# SymphonyLights_MCU_v1_0.net
KiCad netlist of a schematic drawn in Altium Designer
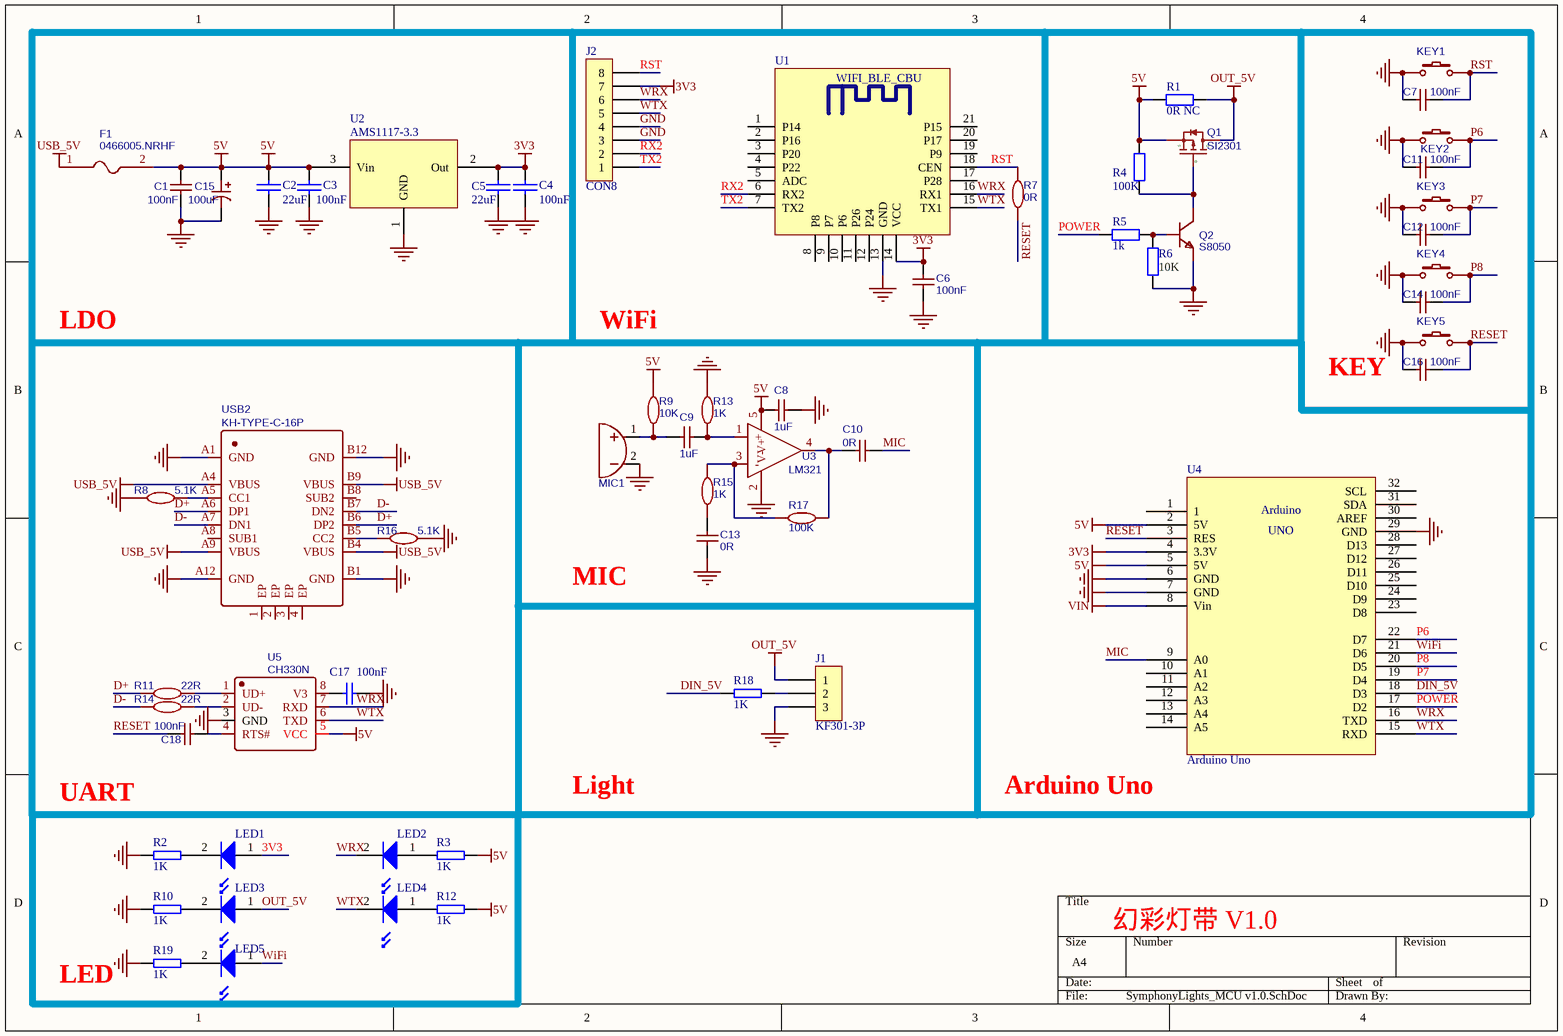
[diagram p0: SymphonyLights_MCU v1.0.SchDoc]

(export (version "E")
  (design (tool "Eeschema 10.0.6"))
  (components
    (comp (ref "C1")
      (value "100nF")
      (footprint "0805C")
      (fields
        (field (name "BOM_MANUFACTURER PART") "0805B104K500NT")
        (field (name "BOM_SUPPLIER PART") "C38141")
      )
      (libsource (lib "altium-import") (part "root_1_100nF_"))
    )
    (comp (ref "C2")
      (value "22uF")
      (footprint "0805C")
      (description "Capacitor")
      (libsource (lib "昊华元件库sch") (part "CAP"))
    )
    (comp (ref "C3")
      (value "100nF")
      (footprint "0805C")
      (description "Capacitor")
      (libsource (lib "昊华元件库sch") (part "CAP"))
    )
    (comp (ref "C4")
      (value "100nF")
      (footprint "0805C")
      (description "Capacitor")
      (libsource (lib "昊华元件库sch") (part "CAP"))
    )
    (comp (ref "C5")
      (value "22uF")
      (footprint "0805C")
      (description "Capacitor")
      (libsource (lib "昊华元件库sch") (part "CAP"))
    )
    (comp (ref "C6")
      (value "100nF")
      (footprint "0805C")
      (fields
        (field (name "BOM_MANUFACTURER PART") "0805B104K500NT")
        (field (name "BOM_SUPPLIER PART") "C38141")
      )
      (libsource (lib "altium-import") (part "root_1_100nF_"))
    )
    (comp (ref "C7")
      (value "100nF")
      (footprint "0805C")
      (fields
        (field (name "BOM_MANUFACTURER PART") "0805B104K500NT")
        (field (name "BOM_SUPPLIER PART") "C38141")
      )
      (libsource (lib "altium-import") (part "root_0_100nF_"))
    )
    (comp (ref "C8")
      (value "1uF")
      (footprint "0805C")
      (fields
        (field (name "BOM_MANUFACTURER PART") "0805B104K500NT")
        (field (name "BOM_SUPPLIER PART") "C38141")
      )
      (libsource (lib "altium-import") (part "root_0_100nF_"))
    )
    (comp (ref "C9")
      (value "1uF")
      (footprint "0805C")
      (fields
        (field (name "BOM_MANUFACTURER PART") "0805B104K500NT")
        (field (name "BOM_SUPPLIER PART") "C38141")
      )
      (libsource (lib "altium-import") (part "root_2_100nF_"))
    )
    (comp (ref "C10")
      (value "0R")
      (footprint "0805C")
      (fields
        (field (name "BOM_MANUFACTURER PART") "0805B104K500NT")
        (field (name "BOM_SUPPLIER PART") "C38141")
      )
      (libsource (lib "altium-import") (part "root_2_100nF_"))
    )
    (comp (ref "C11")
      (value "100nF")
      (footprint "0805C")
      (fields
        (field (name "BOM_MANUFACTURER PART") "0805B104K500NT")
        (field (name "BOM_SUPPLIER PART") "C38141")
      )
      (libsource (lib "altium-import") (part "root_0_100nF_"))
    )
    (comp (ref "C12")
      (value "100nF")
      (footprint "0805C")
      (fields
        (field (name "BOM_MANUFACTURER PART") "0805B104K500NT")
        (field (name "BOM_SUPPLIER PART") "C38141")
      )
      (libsource (lib "altium-import") (part "root_0_100nF_"))
    )
    (comp (ref "C13")
      (value "0R")
      (footprint "0805C")
      (fields
        (field (name "BOM_MANUFACTURER PART") "0805B104K500NT")
        (field (name "BOM_SUPPLIER PART") "C38141")
      )
      (libsource (lib "altium-import") (part "root_3_100nF_"))
    )
    (comp (ref "C14")
      (value "100nF")
      (footprint "0805C")
      (fields
        (field (name "BOM_MANUFACTURER PART") "0805B104K500NT")
        (field (name "BOM_SUPPLIER PART") "C38141")
      )
      (libsource (lib "altium-import") (part "root_0_100nF_"))
    )
    (comp (ref "C15")
      (value "100uF")
      (footprint "CAP-TH_BD6.3-P2.50-D1.0-FD")
      (fields
        (field (name "BOM_SUPPLIER PART") "C723077")
        (field (name "BOM_MANUFACTURER PART") "8101LCMAA08E2RR00O")
        (field (name "CONTRIBUTOR") "LCSC")
      )
      (libsource (lib "altium-import") (part "root_3_8101LCMAA08E2RR00O_"))
    )
    (comp (ref "C16")
      (value "100nF")
      (footprint "0805C")
      (fields
        (field (name "BOM_MANUFACTURER PART") "0805B104K500NT")
        (field (name "BOM_SUPPLIER PART") "C38141")
      )
      (libsource (lib "altium-import") (part "root_0_100nF_"))
    )
    (comp (ref "C17")
      (value "100nF")
      (footprint "0805C")
      (description "普通电容")
      (libsource (lib "RFID_RC632") (part "Cap"))
    )
    (comp (ref "C18")
      (value "100nF")
      (footprint "0805C")
      (fields
        (field (name "BOM_MANUFACTURER PART") "0805B104K500NT")
        (field (name "BOM_SUPPLIER PART") "C38141")
      )
      (libsource (lib "altium-import") (part "root_0_100nF_"))
    )
    (comp (ref "F1")
      (value "0466005.NRHF")
      (footprint "1206F")
      (fields (field (name "BOM_SUPPLIER PART") "C57525"))
      (libsource (lib "altium-import") (part "root_0_0466005.NRHF_"))
    )
    (comp (ref "J1")
      (value "KF301-3P")
      (footprint "SIP3 - 2.54")
      (description "Connector")
      (libsource (lib "小马元件库sch") (part "CON3"))
    )
    (comp (ref "J2")
      (value "CON8")
      (footprint "HDR1X8Z")
      (description "Connector")
      (libsource (lib "小马元件库sch") (part "CON8"))
    )
    (comp (ref "KEY1")
      (value "RESET")
      (footprint "按键")
      (fields
        (field (name "BOM_SUPPLIER PART") "C118141")
        (field (name "BOM_MANUFACTURER PART") "K2-1107ST-A4SW-06")
        (field (name "CONTRIBUTOR") "LCEDA_Lib")
      )
      (libsource (lib "altium-import") (part "root_2_mirrored__"))
    )
    (comp (ref "KEY2")
      (value "场景")
      (footprint "按键")
      (fields
        (field (name "BOM_SUPPLIER PART") "C118141")
        (field (name "BOM_MANUFACTURER PART") "K2-1107ST-A4SW-06")
        (field (name "CONTRIBUTOR") "LCEDA_Lib")
      )
      (libsource (lib "altium-import") (part "root_2__"))
    )
    (comp (ref "KEY3")
      (value "音乐")
      (footprint "按键")
      (fields
        (field (name "BOM_SUPPLIER PART") "C118141")
        (field (name "BOM_MANUFACTURER PART") "K2-1107ST-A4SW-06")
        (field (name "CONTRIBUTOR") "LCEDA_Lib")
      )
      (libsource (lib "altium-import") (part "root_2_mirrored__"))
    )
    (comp (ref "KEY4")
      (value "开关")
      (footprint "按键")
      (fields
        (field (name "BOM_SUPPLIER PART") "C118141")
        (field (name "BOM_MANUFACTURER PART") "K2-1107ST-A4SW-06")
        (field (name "CONTRIBUTOR") "LCEDA_Lib")
      )
      (libsource (lib "altium-import") (part "root_2_mirrored__"))
    )
    (comp (ref "KEY5")
      (value "开关")
      (footprint "按键")
      (fields
        (field (name "BOM_SUPPLIER PART") "C118141")
        (field (name "BOM_MANUFACTURER PART") "K2-1107ST-A4SW-06")
        (field (name "CONTRIBUTOR") "LCEDA_Lib")
      )
      (libsource (lib "altium-import") (part "root_2_mirrored__"))
    )
    (comp (ref "LED1")
      (value "LED")
      (footprint "0805LED")
      (fields (field (name "PUBLISHER") "*"))
      (libsource (lib "小马元件库sch") (part "LED"))
    )
    (comp (ref "LED2")
      (value "LED")
      (footprint "0805LED")
      (fields (field (name "PUBLISHER") "*"))
      (libsource (lib "小马元件库sch") (part "LED"))
    )
    (comp (ref "LED3")
      (value "LED")
      (footprint "0805LED")
      (fields (field (name "PUBLISHER") "*"))
      (libsource (lib "小马元件库sch") (part "LED"))
    )
    (comp (ref "LED4")
      (value "LED")
      (footprint "0805LED")
      (fields (field (name "PUBLISHER") "*"))
      (libsource (lib "小马元件库sch") (part "LED"))
    )
    (comp (ref "LED5")
      (value "LED")
      (footprint "0805LED")
      (fields (field (name "PUBLISHER") "*"))
      (libsource (lib "小马元件库sch") (part "LED"))
    )
    (comp (ref "MIC1")
      (value "GMI6050P-66DB")
      (footprint "MIC-TH_BD6.0-P1.90-D0.4-L-RD")
      (fields (field (name "BOM_SUPPLIER PART") "C233954") (field (name "CONTRIBUTOR") "LCSC"))
      (libsource (lib "altium-import") (part "root_3_mirrored_GMI6050P-66DB_"))
    )
    (comp (ref "Q1")
      (value "SI2301")
      (footprint "SOT-23(SOT-23-3)")
      (fields (field (name "BOM_SUPPLIER PART") "C181086") (field (name "CONTRIBUTOR") "lengyuefeng"))
      (libsource (lib "altium-import") (part "root_1_mirrored_SI2301_"))
    )
    (comp (ref "Q2")
      (value "S8050")
      (footprint "SOT-23(SOT-23-3)")
      (fields (field (name "BOM_SUPPLIER PART") "C2146"))
      (libsource (lib "altium-import") (part "root_0_S8050_"))
    )
    (comp (ref "R1")
      (value "0R NC")
      (footprint "0805R")
      (description "Resistor")
      (fields (field (name "PUBLISHER") "Altium Limited"))
      (libsource (lib "*") (part "Res2"))
    )
    (comp (ref "R2") (value "1K") (footprint "0805R") (libsource (lib "昊华元件库sch") (part "RES5")))
    (comp (ref "R3") (value "1K") (footprint "0805R") (libsource (lib "昊华元件库sch") (part "RES5")))
    (comp (ref "R4")
      (value "100K")
      (footprint "0805R")
      (description "Resistor")
      (fields (field (name "PUBLISHER") "Altium Limited"))
      (libsource (lib "") (part "Res2_2"))
    )
    (comp (ref "R5")
      (value "1k")
      (footprint "0805R")
      (description "Resistor")
      (fields (field (name "PUBLISHER") "Altium Limited"))
      (libsource (lib "*") (part "Res2"))
    )
    (comp (ref "R6")
      (value "10K")
      (footprint "0805R")
      (description "Resistor")
      (fields (field (name "PUBLISHER") "Altium Limited"))
      (libsource (lib "") (part "Res2_1"))
    )
    (comp (ref "R7")
      (value "0R")
      (footprint "0805R")
      (fields
        (field (name "BOM_SUPPLIER PART") "C328298")
        (field (name "BOM_MANUFACTURER PART") "AECR0402F10K0K9")
        (field (name "CONTRIBUTOR") "LCSC")
      )
      (libsource (lib "altium-import") (part "root_3_10K_"))
    )
    (comp (ref "R8")
      (value "5.1K")
      (footprint "0805R")
      (fields
        (field (name "BOM_SUPPLIER PART") "C328298")
        (field (name "BOM_MANUFACTURER PART") "AECR0402F10K0K9")
        (field (name "CONTRIBUTOR") "LCSC")
      )
      (libsource (lib "altium-import") (part "root_0_10K_"))
    )
    (comp (ref "R9")
      (value "10K")
      (footprint "0805R")
      (fields
        (field (name "BOM_SUPPLIER PART") "C328298")
        (field (name "BOM_MANUFACTURER PART") "AECR0402F10K0K9")
        (field (name "CONTRIBUTOR") "LCSC")
      )
      (libsource (lib "altium-import") (part "root_3_10K_"))
    )
    (comp (ref "R10") (value "1K") (footprint "0805R") (libsource (lib "昊华元件库sch") (part "RES5")))
    (comp (ref "R11")
      (value "22R")
      (footprint "0805R")
      (fields
        (field (name "BOM_SUPPLIER PART") "C328298")
        (field (name "BOM_MANUFACTURER PART") "AECR0402F10K0K9")
        (field (name "CONTRIBUTOR") "LCSC")
      )
      (libsource (lib "altium-import") (part "root_2_10K_"))
    )
    (comp (ref "R12") (value "1K") (footprint "0805R") (libsource (lib "昊华元件库sch") (part "RES5")))
    (comp (ref "R13")
      (value "1K")
      (footprint "0805R")
      (fields
        (field (name "BOM_SUPPLIER PART") "C328298")
        (field (name "BOM_MANUFACTURER PART") "AECR0402F10K0K9")
        (field (name "CONTRIBUTOR") "LCSC")
      )
      (libsource (lib "altium-import") (part "root_3_10K_"))
    )
    (comp (ref "R14")
      (value "22R")
      (footprint "0805R")
      (fields
        (field (name "BOM_SUPPLIER PART") "C328298")
        (field (name "BOM_MANUFACTURER PART") "AECR0402F10K0K9")
        (field (name "CONTRIBUTOR") "LCSC")
      )
      (libsource (lib "altium-import") (part "root_2_10K_"))
    )
    (comp (ref "R15")
      (value "1K")
      (footprint "0805R")
      (fields
        (field (name "BOM_SUPPLIER PART") "C328298")
        (field (name "BOM_MANUFACTURER PART") "AECR0402F10K0K9")
        (field (name "CONTRIBUTOR") "LCSC")
      )
      (libsource (lib "altium-import") (part "root_1_10K_"))
    )
    (comp (ref "R16")
      (value "5.1K")
      (footprint "0805R")
      (fields
        (field (name "BOM_SUPPLIER PART") "C328298")
        (field (name "BOM_MANUFACTURER PART") "AECR0402F10K0K9")
        (field (name "CONTRIBUTOR") "LCSC")
      )
      (libsource (lib "altium-import") (part "root_2_10K_"))
    )
    (comp (ref "R17")
      (value "100K")
      (footprint "0805R")
      (fields
        (field (name "BOM_SUPPLIER PART") "C328298")
        (field (name "BOM_MANUFACTURER PART") "AECR0402F10K0K9")
        (field (name "CONTRIBUTOR") "LCSC")
      )
      (libsource (lib "altium-import") (part "root_0_10K_"))
    )
    (comp (ref "R18") (value "1K") (footprint "0805R") (libsource (lib "昊华元件库sch") (part "RES5")))
    (comp (ref "R19") (value "1K") (footprint "0805R") (libsource (lib "昊华元件库sch") (part "RES5")))
    (comp (ref "U1")
      (value "WIFI_BLE_CBU")
      (footprint "WIFI_BLE_CBU")
      (description "Module")
      (libsource (lib "TYModeSchlib V03") (part "WIFI_BLE_CBU"))
    )
    (comp (ref "U2") (value "AMS1117-3.3") (footprint "SOT-223") (libsource (lib "mylib") (part "GM1117")))
    (comp (ref "U3")
      (value "LM321")
      (footprint "SOT-23-5")
      (fields (field (name "CONTRIBUTOR") "KiCAD"))
      (libsource (lib "altium-import") (part "root_0_LM321_"))
    )
    (comp (ref "U4")
      (value "Arduino Uno")
      (footprint "Arduino UNO-2")
      (libsource (lib "Arduino") (part "Arduino Uno"))
    )
    (comp (ref "U5")
      (value "CH330N")
      (footprint "SOP-8_L4.9-W3.9-P1.27-LS6.0-BL")
      (fields (field (name "BOM_SUPPLIER PART") "C108996"))
      (libsource (lib "altium-import") (part "root_0_CH330N_"))
    )
    (comp (ref "USB2")
      (value "KH-TYPE-C-16P")
      (footprint "USB-C-SMD_KH-TYPE-C-16P")
      (fields (field (name "BOM_SUPPLIER PART") "C709357") (field (name "CONTRIBUTOR") "LCSC"))
      (libsource (lib "altium-import") (part "root_0_KH-TYPE-C-16P_"))
    )
  )
  (nets
    (net (code "1") (name "/D+") (class "Default")
      (node (ref "R11") (pin "2") (pinfunction "2_2") (pintype "passive"))
      (node (ref "USB2") (pin "A6") (pinfunction "DP1_A6") (pintype "passive"))
      (node (ref "USB2") (pin "B6") (pinfunction "DP2_B6") (pintype "passive"))
    )
    (net (code "2") (name "/D-") (class "Default")
      (node (ref "R14") (pin "2") (pinfunction "2_2") (pintype "passive"))
      (node (ref "USB2") (pin "A7") (pinfunction "DN1_A7") (pintype "passive"))
      (node (ref "USB2") (pin "B7") (pinfunction "DN2_B7") (pintype "passive"))
    )
    (net (code "3") (name "/DIN_5V") (class "Default")
      (node (ref "R18") (pin "1") (pinfunction "1_1") (pintype "passive"))
      (node (ref "U4") (pin "18") (pinfunction "D3_18") (pintype "passive"))
    )
    (net (code "4") (name "/MIC") (class "Default")
      (node (ref "C10") (pin "1") (pinfunction "1_1") (pintype "passive"))
      (node (ref "U4") (pin "9") (pinfunction "A0_9") (pintype "passive"))
    )
    (net (code "5") (name "/P6") (class "Default")
      (node (ref "C11") (pin "2") (pinfunction "2_2") (pintype "passive"))
      (node (ref "KEY2") (pin "2") (pinfunction "2_2") (pintype "passive"))
      (node (ref "U4") (pin "22") (pinfunction "D7_22") (pintype "passive"))
    )
    (net (code "6") (name "/P7") (class "Default")
      (node (ref "C12") (pin "2") (pinfunction "2_2") (pintype "passive"))
      (node (ref "KEY3") (pin "1") (pinfunction "1_1") (pintype "passive"))
      (node (ref "U4") (pin "19") (pinfunction "D4_19") (pintype "passive"))
    )
    (net (code "7") (name "/P8") (class "Default")
      (node (ref "C14") (pin "2") (pinfunction "2_2") (pintype "passive"))
      (node (ref "KEY4") (pin "1") (pinfunction "1_1") (pintype "passive"))
      (node (ref "U4") (pin "20") (pinfunction "D5_20") (pintype "passive"))
    )
    (net (code "8") (name "/POWER") (class "Default")
      (node (ref "R5") (pin "1") (pinfunction "1_1") (pintype "passive"))
      (node (ref "U4") (pin "17") (pinfunction "D2_17") (pintype "passive"))
    )
    (net (code "9") (name "/RESET") (class "Default")
      (node (ref "C16") (pin "2") (pinfunction "2_2") (pintype "passive"))
      (node (ref "C18") (pin "1") (pinfunction "1_1") (pintype "passive"))
      (node (ref "KEY5") (pin "1") (pinfunction "1_1") (pintype "passive"))
      (node (ref "R7") (pin "2") (pinfunction "2_2") (pintype "passive"))
      (node (ref "U4") (pin "3") (pinfunction "RES_3") (pintype "passive"))
    )
    (net (code "10") (name "/RST") (class "Default")
      (node (ref "C7") (pin "2") (pinfunction "2_2") (pintype "passive"))
      (node (ref "J2") (pin "8") (pinfunction "8_8") (pintype "passive"))
      (node (ref "KEY1") (pin "1") (pinfunction "1_1") (pintype "passive"))
      (node (ref "R7") (pin "1") (pinfunction "1_1") (pintype "passive"))
      (node (ref "U1") (pin "18") (pinfunction "CEN_18") (pintype "passive"))
    )
    (net (code "11") (name "/RX2") (class "Default")
      (node (ref "J2") (pin "2") (pinfunction "2_2") (pintype "passive"))
      (node (ref "U1") (pin "6") (pinfunction "RX2_6") (pintype "passive"))
    )
    (net (code "12") (name "/TX2") (class "Default")
      (node (ref "J2") (pin "1") (pinfunction "1_1") (pintype "passive"))
      (node (ref "U1") (pin "7") (pinfunction "TX2_7") (pintype "passive"))
    )
    (net (code "13") (name "/WRX") (class "Default")
      (node (ref "J2") (pin "6") (pinfunction "6_6") (pintype "passive"))
      (node (ref "LED2") (pin "2") (pinfunction "2_2") (pintype "passive"))
      (node (ref "U1") (pin "16") (pinfunction "RX1_16") (pintype "passive"))
      (node (ref "U4") (pin "16") (pinfunction "TXD_16") (pintype "passive"))
      (node (ref "U5") (pin "7") (pinfunction "RXD_7") (pintype "passive"))
    )
    (net (code "14") (name "/WTX") (class "Default")
      (node (ref "J2") (pin "5") (pinfunction "5_5") (pintype "passive"))
      (node (ref "LED4") (pin "2") (pinfunction "2_2") (pintype "passive"))
      (node (ref "U1") (pin "15") (pinfunction "TX1_15") (pintype "passive"))
      (node (ref "U4") (pin "15") (pinfunction "RXD_15") (pintype "passive"))
      (node (ref "U5") (pin "6") (pinfunction "TXD_6") (pintype "passive"))
    )
    (net (code "15") (name "/WiFi") (class "Default")
      (node (ref "LED5") (pin "1") (pinfunction "1_1") (pintype "passive"))
      (node (ref "U4") (pin "21") (pinfunction "D6_21") (pintype "passive"))
    )
    (net (code "16") (name "3V3") (class "Default")
      (node (ref "C4") (pin "1") (pinfunction "1_1") (pintype "passive"))
      (node (ref "C5") (pin "1") (pinfunction "1_1") (pintype "passive"))
      (node (ref "C6") (pin "2") (pinfunction "2_2") (pintype "passive"))
      (node (ref "J2") (pin "7") (pinfunction "7_7") (pintype "passive"))
      (node (ref "LED1") (pin "1") (pinfunction "1_1") (pintype "passive"))
      (node (ref "U1") (pin "14") (pinfunction "VCC_14") (pintype "passive"))
      (node (ref "U2") (pin "2") (pinfunction "Out_2") (pintype "passive"))
      (node (ref "U4") (pin "4") (pinfunction "3.3V_4") (pintype "passive"))
    )
    (net (code "17") (name "5V") (class "Default")
      (node (ref "C1") (pin "2") (pinfunction "2_2") (pintype "passive"))
      (node (ref "C15") (pin "1") (pinfunction "1_1") (pintype "passive"))
      (node (ref "C2") (pin "1") (pinfunction "1_1") (pintype "passive"))
      (node (ref "C3") (pin "1") (pinfunction "1_1") (pintype "passive"))
      (node (ref "C8") (pin "1") (pinfunction "1_1") (pintype "passive"))
      (node (ref "F1") (pin "2") (pinfunction "2_2") (pintype "passive"))
      (node (ref "Q1") (pin "2") (pinfunction "S_2") (pintype "passive"))
      (node (ref "R1") (pin "1") (pinfunction "1_1") (pintype "passive"))
      (node (ref "R12") (pin "1") (pinfunction "1_1") (pintype "passive"))
      (node (ref "R3") (pin "1") (pinfunction "1_1") (pintype "passive"))
      (node (ref "R4") (pin "2") (pinfunction "2_2") (pintype "passive"))
      (node (ref "R9") (pin "1") (pinfunction "1_1") (pintype "passive"))
      (node (ref "U2") (pin "3") (pinfunction "Vin_3") (pintype "passive"))
      (node (ref "U3") (pin "5") (pinfunction "V+_5") (pintype "passive"))
      (node (ref "U4") (pin "2") (pinfunction "5V_2") (pintype "passive"))
      (node (ref "U4") (pin "5") (pinfunction "5V_5") (pintype "passive"))
      (node (ref "U5") (pin "5") (pinfunction "VCC_5") (pintype "passive"))
    )
    (net (code "18") (name "GND") (class "Default")
      (node (ref "C1") (pin "1") (pinfunction "1_1") (pintype "passive"))
      (node (ref "C11") (pin "1") (pinfunction "1_1") (pintype "passive"))
      (node (ref "C12") (pin "1") (pinfunction "1_1") (pintype "passive"))
      (node (ref "C13") (pin "2") (pinfunction "2_2") (pintype "passive"))
      (node (ref "C14") (pin "1") (pinfunction "1_1") (pintype "passive"))
      (node (ref "C15") (pin "2") (pinfunction "2_2") (pintype "passive"))
      (node (ref "C16") (pin "1") (pinfunction "1_1") (pintype "passive"))
      (node (ref "C17") (pin "1") (pinfunction "1_1") (pintype "passive"))
      (node (ref "C2") (pin "2") (pinfunction "2_2") (pintype "passive"))
      (node (ref "C3") (pin "2") (pinfunction "2_2") (pintype "passive"))
      (node (ref "C4") (pin "2") (pinfunction "2_2") (pintype "passive"))
      (node (ref "C5") (pin "2") (pinfunction "2_2") (pintype "passive"))
      (node (ref "C6") (pin "1") (pinfunction "1_1") (pintype "passive"))
      (node (ref "C7") (pin "1") (pinfunction "1_1") (pintype "passive"))
      (node (ref "C8") (pin "2") (pinfunction "2_2") (pintype "passive"))
      (node (ref "J1") (pin "3") (pinfunction "3_3") (pintype "passive"))
      (node (ref "J2") (pin "3") (pinfunction "3_3") (pintype "passive"))
      (node (ref "J2") (pin "4") (pinfunction "4_4") (pintype "passive"))
      (node (ref "KEY1") (pin "2") (pinfunction "2_2") (pintype "passive"))
      (node (ref "KEY2") (pin "1") (pinfunction "1_1") (pintype "passive"))
      (node (ref "KEY3") (pin "2") (pinfunction "2_2") (pintype "passive"))
      (node (ref "KEY4") (pin "2") (pinfunction "2_2") (pintype "passive"))
      (node (ref "KEY5") (pin "2") (pinfunction "2_2") (pintype "passive"))
      (node (ref "MIC1") (pin "2") (pinfunction "2_2") (pintype "passive"))
      (node (ref "Q2") (pin "2") (pinfunction "E_2") (pintype "passive"))
      (node (ref "R10") (pin "2") (pinfunction "2_2") (pintype "passive"))
      (node (ref "R13") (pin "1") (pinfunction "1_1") (pintype "passive"))
      (node (ref "R16") (pin "1") (pinfunction "1_1") (pintype "passive"))
      (node (ref "R19") (pin "2") (pinfunction "2_2") (pintype "passive"))
      (node (ref "R2") (pin "2") (pinfunction "2_2") (pintype "passive"))
      (node (ref "R6") (pin "2") (pinfunction "2_2") (pintype "passive"))
      (node (ref "R8") (pin "1") (pinfunction "1_1") (pintype "passive"))
      (node (ref "U1") (pin "13") (pinfunction "GND_13") (pintype "passive"))
      (node (ref "U2") (pin "1") (pinfunction "GND_1") (pintype "passive"))
      (node (ref "U3") (pin "2") (pinfunction "V-_2") (pintype "passive"))
      (node (ref "U4") (pin "29") (pinfunction "GND_29") (pintype "passive"))
      (node (ref "U4") (pin "6") (pinfunction "GND_6") (pintype "passive"))
      (node (ref "U4") (pin "7") (pinfunction "GND_7") (pintype "passive"))
      (node (ref "U5") (pin "3") (pinfunction "GND_3") (pintype "passive"))
      (node (ref "USB2") (pin "A1") (pinfunction "GND_A1") (pintype "passive"))
      (node (ref "USB2") (pin "A12") (pinfunction "GND_A12") (pintype "passive"))
      (node (ref "USB2") (pin "B1") (pinfunction "GND_B1") (pintype "passive"))
      (node (ref "USB2") (pin "B12") (pinfunction "GND_B12") (pintype "passive"))
    )
    (net (code "19") (name "Net-(C9-Pad2)") (class "Default")
      (node (ref "C9") (pin "2") (pinfunction "2_2") (pintype "passive"))
      (node (ref "MIC1") (pin "1") (pinfunction "1_1") (pintype "passive"))
      (node (ref "R9") (pin "2") (pinfunction "2_2") (pintype "passive"))
    )
    (net (code "20") (name "Net-(C10-Pad2)") (class "Default")
      (node (ref "C10") (pin "2") (pinfunction "2_2") (pintype "passive"))
      (node (ref "R17") (pin "2") (pinfunction "2_2") (pintype "passive"))
      (node (ref "U3") (pin "4") (pintype "passive"))
    )
    (net (code "21") (name "Net-(C13-Pad1)") (class "Default")
      (node (ref "C13") (pin "1") (pinfunction "1_1") (pintype "passive"))
      (node (ref "R15") (pin "1") (pinfunction "1_1") (pintype "passive"))
    )
    (net (code "22") (name "Net-(J1-Pad2)") (class "Default")
      (node (ref "J1") (pin "2") (pinfunction "2_2") (pintype "passive"))
      (node (ref "R18") (pin "2") (pinfunction "2_2") (pintype "passive"))
    )
    (net (code "23") (name "Net-(LED1-Pad2)") (class "Default")
      (node (ref "LED1") (pin "2") (pinfunction "2_2") (pintype "passive"))
      (node (ref "R2") (pin "1") (pinfunction "1_1") (pintype "passive"))
    )
    (net (code "24") (name "Net-(LED2-Pad1)") (class "Default")
      (node (ref "LED2") (pin "1") (pinfunction "1_1") (pintype "passive"))
      (node (ref "R3") (pin "2") (pinfunction "2_2") (pintype "passive"))
    )
    (net (code "25") (name "Net-(LED3-Pad2)") (class "Default")
      (node (ref "LED3") (pin "2") (pinfunction "2_2") (pintype "passive"))
      (node (ref "R10") (pin "1") (pinfunction "1_1") (pintype "passive"))
    )
    (net (code "26") (name "Net-(LED4-Pad1)") (class "Default")
      (node (ref "LED4") (pin "1") (pinfunction "1_1") (pintype "passive"))
      (node (ref "R12") (pin "2") (pinfunction "2_2") (pintype "passive"))
    )
    (net (code "27") (name "Net-(LED5-Pad2)") (class "Default")
      (node (ref "LED5") (pin "2") (pinfunction "2_2") (pintype "passive"))
      (node (ref "R19") (pin "1") (pinfunction "1_1") (pintype "passive"))
    )
    (net (code "28") (name "Net-(Q1-G)") (class "Default")
      (node (ref "Q1") (pin "1") (pinfunction "G_1") (pintype "passive"))
      (node (ref "Q2") (pin "3") (pinfunction "C_3") (pintype "passive"))
      (node (ref "R4") (pin "1") (pinfunction "1_1") (pintype "passive"))
    )
    (net (code "29") (name "Net-(Q2-B)") (class "Default")
      (node (ref "Q2") (pin "1") (pinfunction "B_1") (pintype "passive"))
      (node (ref "R5") (pin "2") (pinfunction "2_2") (pintype "passive"))
      (node (ref "R6") (pin "1") (pinfunction "1_1") (pintype "passive"))
    )
    (net (code "30") (name "Net-(U3-+)") (class "Default")
      (node (ref "C9") (pin "1") (pinfunction "1_1") (pintype "passive"))
      (node (ref "R13") (pin "2") (pinfunction "2_2") (pintype "passive"))
      (node (ref "U3") (pin "1") (pinfunction "+_1") (pintype "passive"))
    )
    (net (code "31") (name "Net-(U3--)") (class "Default")
      (node (ref "R15") (pin "2") (pinfunction "2_2") (pintype "passive"))
      (node (ref "R17") (pin "1") (pinfunction "1_1") (pintype "passive"))
      (node (ref "U3") (pin "3") (pinfunction "-_3") (pintype "passive"))
    )
    (net (code "32") (name "Net-(U5-RTS#)") (class "Default")
      (node (ref "C18") (pin "2") (pinfunction "2_2") (pintype "passive"))
      (node (ref "U5") (pin "4") (pinfunction "RTS#_4") (pintype "passive"))
    )
    (net (code "33") (name "Net-(U5-UD+)") (class "Default")
      (node (ref "R11") (pin "1") (pinfunction "1_1") (pintype "passive"))
      (node (ref "U5") (pin "1") (pinfunction "UD+_1") (pintype "passive"))
    )
    (net (code "34") (name "Net-(U5-UD-)") (class "Default")
      (node (ref "R14") (pin "1") (pinfunction "1_1") (pintype "passive"))
      (node (ref "U5") (pin "2") (pinfunction "UD-_2") (pintype "passive"))
    )
    (net (code "35") (name "Net-(U5-V3)") (class "Default")
      (node (ref "C17") (pin "2") (pinfunction "2_2") (pintype "passive"))
      (node (ref "U5") (pin "8") (pinfunction "V3_8") (pintype "passive"))
    )
    (net (code "36") (name "Net-(USB2-CC1)") (class "Default")
      (node (ref "R8") (pin "2") (pinfunction "2_2") (pintype "passive"))
      (node (ref "USB2") (pin "A5") (pinfunction "CC1_A5") (pintype "passive"))
    )
    (net (code "37") (name "Net-(USB2-CC2)") (class "Default")
      (node (ref "R16") (pin "2") (pinfunction "2_2") (pintype "passive"))
      (node (ref "USB2") (pin "B5") (pinfunction "CC2_B5") (pintype "passive"))
    )
    (net (code "38") (name "OUT_5V") (class "Default")
      (node (ref "J1") (pin "1") (pinfunction "1_1") (pintype "passive"))
      (node (ref "LED3") (pin "1") (pinfunction "1_1") (pintype "passive"))
      (node (ref "Q1") (pin "3") (pinfunction "D_3") (pintype "passive"))
      (node (ref "R1") (pin "2") (pinfunction "2_2") (pintype "passive"))
    )
    (net (code "39") (name "USB_5V") (class "Default")
      (node (ref "F1") (pin "1") (pinfunction "1_1") (pintype "passive"))
      (node (ref "USB2") (pin "A4") (pinfunction "VBUS_A4") (pintype "passive"))
      (node (ref "USB2") (pin "A9") (pinfunction "VBUS_A9") (pintype "passive"))
      (node (ref "USB2") (pin "B4") (pinfunction "VBUS_B4") (pintype "passive"))
      (node (ref "USB2") (pin "B9") (pinfunction "VBUS_B9") (pintype "passive"))
    )
    (net (code "40") (name "VIN") (class "Default")
      (node (ref "U4") (pin "8") (pinfunction "Vin_8") (pintype "passive"))
    )
    (net (code "41") (name "unconnected-(U1-ADC-Pad5)") (class "Default")
      (node (ref "U1") (pin "5") (pinfunction "ADC_5") (pintype "passive"))
    )
    (net (code "42") (name "unconnected-(U1-P6-Pad10)") (class "Default")
      (node (ref "U1") (pin "10") (pinfunction "P6_10") (pintype "passive"))
    )
    (net (code "43") (name "unconnected-(U1-P7-Pad9)") (class "Default")
      (node (ref "U1") (pin "9") (pinfunction "P7_9") (pintype "passive"))
    )
    (net (code "44") (name "unconnected-(U1-P8-Pad8)") (class "Default")
      (node (ref "U1") (pin "8") (pinfunction "P8_8") (pintype "passive"))
    )
    (net (code "45") (name "unconnected-(U1-P9-Pad19)") (class "Default")
      (node (ref "U1") (pin "19") (pinfunction "P9_19") (pintype "passive"))
    )
    (net (code "46") (name "unconnected-(U1-P14-Pad1)") (class "Default")
      (node (ref "U1") (pin "1") (pinfunction "P14_1") (pintype "passive"))
    )
    (net (code "47") (name "unconnected-(U1-P15-Pad21)") (class "Default")
      (node (ref "U1") (pin "21") (pinfunction "P15_21") (pintype "passive"))
    )
    (net (code "48") (name "unconnected-(U1-P16-Pad2)") (class "Default")
      (node (ref "U1") (pin "2") (pinfunction "P16_2") (pintype "passive"))
    )
    (net (code "49") (name "unconnected-(U1-P17-Pad20)") (class "Default")
      (node (ref "U1") (pin "20") (pinfunction "P17_20") (pintype "passive"))
    )
    (net (code "50") (name "unconnected-(U1-P20-Pad3)") (class "Default")
      (node (ref "U1") (pin "3") (pinfunction "P20_3") (pintype "passive"))
    )
    (net (code "51") (name "unconnected-(U1-P22-Pad4)") (class "Default")
      (node (ref "U1") (pin "4") (pinfunction "P22_4") (pintype "passive"))
    )
    (net (code "52") (name "unconnected-(U1-P24-Pad12)") (class "Default")
      (node (ref "U1") (pin "12") (pinfunction "P24_12") (pintype "passive"))
    )
    (net (code "53") (name "unconnected-(U1-P26-Pad11)") (class "Default")
      (node (ref "U1") (pin "11") (pinfunction "P26_11") (pintype "passive"))
    )
    (net (code "54") (name "unconnected-(U1-P28-Pad17)") (class "Default")
      (node (ref "U1") (pin "17") (pinfunction "P28_17") (pintype "passive"))
    )
    (net (code "55") (name "unconnected-(U4-A1-Pad10)") (class "Default")
      (node (ref "U4") (pin "10") (pinfunction "A1_10") (pintype "passive"))
    )
    (net (code "56") (name "unconnected-(U4-A2-Pad11)") (class "Default")
      (node (ref "U4") (pin "11") (pinfunction "A2_11") (pintype "passive"))
    )
    (net (code "57") (name "unconnected-(U4-A3-Pad12)") (class "Default")
      (node (ref "U4") (pin "12") (pinfunction "A3_12") (pintype "passive"))
    )
    (net (code "58") (name "unconnected-(U4-A4-Pad13)") (class "Default")
      (node (ref "U4") (pin "13") (pinfunction "A4_13") (pintype "passive"))
    )
    (net (code "59") (name "unconnected-(U4-A5-Pad14)") (class "Default")
      (node (ref "U4") (pin "14") (pinfunction "A5_14") (pintype "passive"))
    )
    (net (code "60") (name "unconnected-(U4-AREF-Pad30)") (class "Default")
      (node (ref "U4") (pin "30") (pinfunction "AREF_30") (pintype "passive"))
    )
    (net (code "61") (name "unconnected-(U4-D8-Pad23)") (class "Default")
      (node (ref "U4") (pin "23") (pinfunction "D8_23") (pintype "passive"))
    )
    (net (code "62") (name "unconnected-(U4-D9-Pad24)") (class "Default")
      (node (ref "U4") (pin "24") (pinfunction "D9_24") (pintype "passive"))
    )
    (net (code "63") (name "unconnected-(U4-D10-Pad25)") (class "Default")
      (node (ref "U4") (pin "25") (pinfunction "D10_25") (pintype "passive"))
    )
    (net (code "64") (name "unconnected-(U4-D11-Pad26)") (class "Default")
      (node (ref "U4") (pin "26") (pinfunction "D11_26") (pintype "passive"))
    )
    (net (code "65") (name "unconnected-(U4-D12-Pad27)") (class "Default")
      (node (ref "U4") (pin "27") (pinfunction "D12_27") (pintype "passive"))
    )
    (net (code "66") (name "unconnected-(U4-D13-Pad28)") (class "Default")
      (node (ref "U4") (pin "28") (pinfunction "D13_28") (pintype "passive"))
    )
    (net (code "67") (name "unconnected-(U4-Pad1)") (class "Default")
      (node (ref "U4") (pin "1") (pinfunction "1_1") (pintype "passive"))
    )
    (net (code "68") (name "unconnected-(U4-SCL-Pad32)") (class "Default")
      (node (ref "U4") (pin "32") (pinfunction "SCL_32") (pintype "passive"))
    )
    (net (code "69") (name "unconnected-(U4-SDA-Pad31)") (class "Default")
      (node (ref "U4") (pin "31") (pinfunction "SDA_31") (pintype "passive"))
    )
    (net (code "70") (name "unconnected-(USB2-EP-Pad1)") (class "Default")
      (node (ref "USB2") (pin "1") (pinfunction "EP_1") (pintype "passive"))
    )
    (net (code "71") (name "unconnected-(USB2-EP-Pad2)") (class "Default")
      (node (ref "USB2") (pin "2") (pinfunction "EP_2") (pintype "passive"))
    )
    (net (code "72") (name "unconnected-(USB2-EP-Pad3)") (class "Default")
      (node (ref "USB2") (pin "3") (pinfunction "EP_3") (pintype "passive"))
    )
    (net (code "73") (name "unconnected-(USB2-EP-Pad4)") (class "Default")
      (node (ref "USB2") (pin "4") (pinfunction "EP_4") (pintype "passive"))
    )
    (net (code "74") (name "unconnected-(USB2-SUB1-PadA8)") (class "Default")
      (node (ref "USB2") (pin "A8") (pinfunction "SUB1_A8") (pintype "passive"))
    )
    (net (code "75") (name "unconnected-(USB2-SUB2-PadB8)") (class "Default")
      (node (ref "USB2") (pin "B8") (pinfunction "SUB2_B8") (pintype "passive"))
    )
  )
)
